# MPC23017.net
KiCad netlist of a schematic drawn in Altium Designer
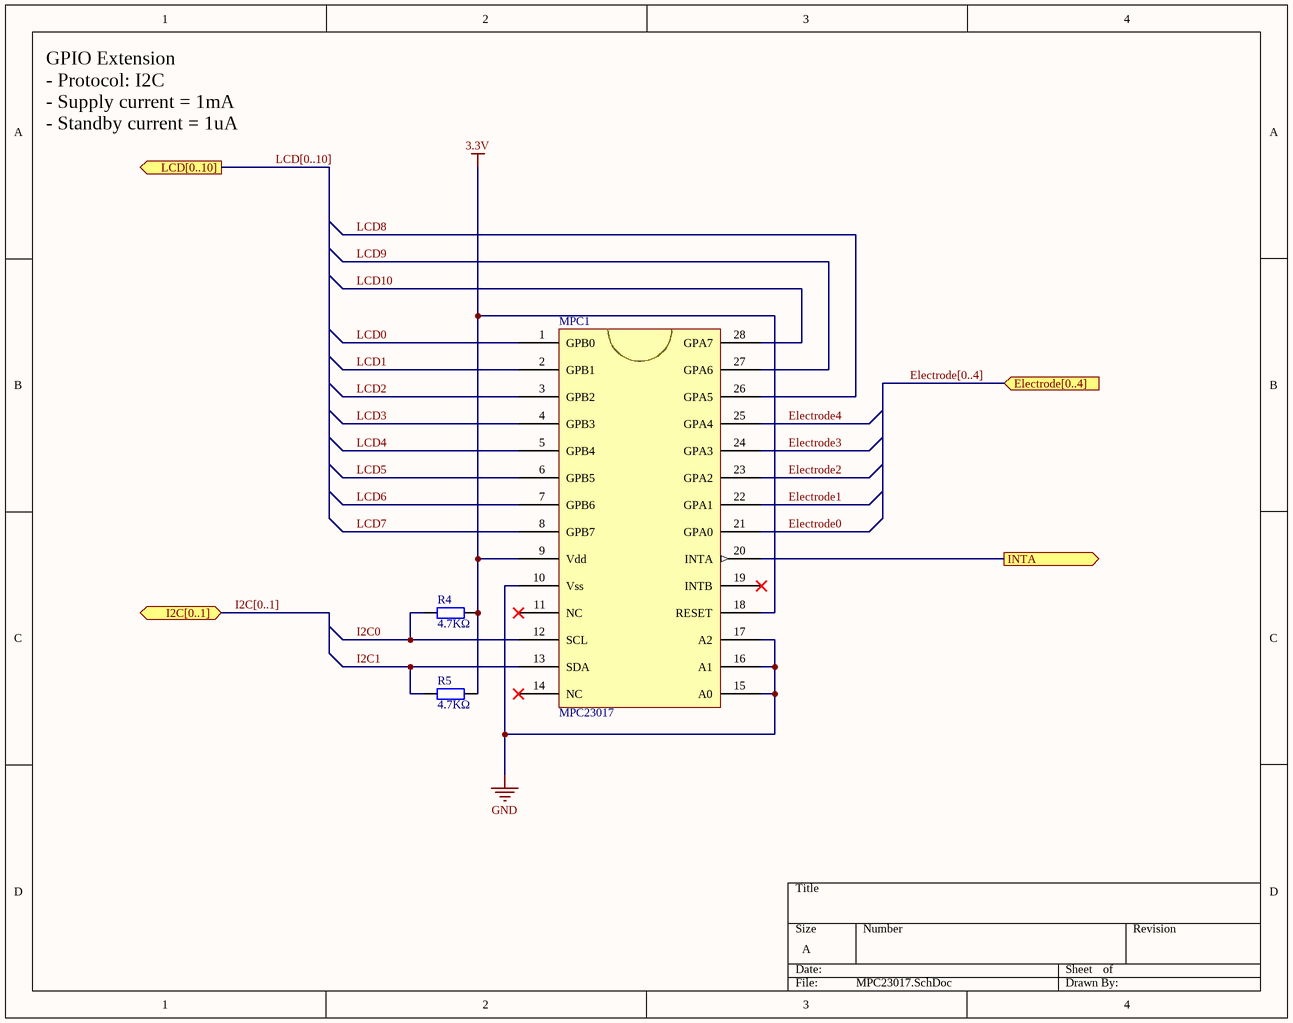
[diagram p0: MPC23017.SchDoc]

(export (version "E")
  (design (tool "Eeschema 10.0.6"))
  (components
    (comp (ref "MPC1") (value "MPC23017") (libsource (lib "MPC23017") (part "Component_1")))
    (comp (ref "R4")
      (value "4.7KΩ")
      (footprint "AXIAL-0.4")
      (description "Resistor")
      (fields (field (name "PUBLISHER") "Altium Limited"))
      (libsource (lib "Miscellaneous Devices") (part "Res2"))
    )
    (comp (ref "R5")
      (value "4.7KΩ")
      (footprint "AXIAL-0.4")
      (description "Resistor")
      (fields (field (name "PUBLISHER") "Altium Limited"))
      (libsource (lib "Miscellaneous Devices") (part "Res2"))
    )
  )
  (nets
    (net (code "1") (name "/Electrode0") (class "Default")
      (node (ref "MPC1") (pin "21") (pinfunction "GPA0_21") (pintype "passive"))
    )
    (net (code "2") (name "/Electrode1") (class "Default")
      (node (ref "MPC1") (pin "22") (pinfunction "GPA1_22") (pintype "passive"))
    )
    (net (code "3") (name "/Electrode2") (class "Default")
      (node (ref "MPC1") (pin "23") (pinfunction "GPA2_23") (pintype "passive"))
    )
    (net (code "4") (name "/Electrode3") (class "Default")
      (node (ref "MPC1") (pin "24") (pinfunction "GPA3_24") (pintype "passive"))
    )
    (net (code "5") (name "/Electrode4") (class "Default")
      (node (ref "MPC1") (pin "25") (pinfunction "GPA4_25") (pintype "passive"))
    )
    (net (code "7") (name "/I2C0") (class "Default")
      (node (ref "MPC1") (pin "12") (pinfunction "SCL_12") (pintype "passive"))
      (node (ref "R4") (pin "2") (pinfunction "2_2") (pintype "passive"))
    )
    (net (code "8") (name "/I2C1") (class "Default")
      (node (ref "MPC1") (pin "13") (pinfunction "SDA_13") (pintype "passive"))
      (node (ref "R5") (pin "2") (pinfunction "2_2") (pintype "passive"))
    )
    (net (code "10") (name "/INTA") (class "Default")
      (node (ref "MPC1") (pin "20") (pinfunction "INTA_20") (pintype "output"))
    )
    (net (code "11") (name "/LCD0") (class "Default")
      (node (ref "MPC1") (pin "1") (pinfunction "GPB0_1") (pintype "passive"))
    )
    (net (code "12") (name "/LCD1") (class "Default")
      (node (ref "MPC1") (pin "2") (pinfunction "GPB1_2") (pintype "passive"))
    )
    (net (code "13") (name "/LCD2") (class "Default")
      (node (ref "MPC1") (pin "3") (pinfunction "GPB2_3") (pintype "passive"))
    )
    (net (code "14") (name "/LCD3") (class "Default")
      (node (ref "MPC1") (pin "4") (pinfunction "GPB3_4") (pintype "passive"))
    )
    (net (code "15") (name "/LCD4") (class "Default")
      (node (ref "MPC1") (pin "5") (pinfunction "GPB4_5") (pintype "passive"))
    )
    (net (code "16") (name "/LCD5") (class "Default")
      (node (ref "MPC1") (pin "6") (pinfunction "GPB5_6") (pintype "passive"))
    )
    (net (code "17") (name "/LCD6") (class "Default")
      (node (ref "MPC1") (pin "7") (pinfunction "GPB6_7") (pintype "passive"))
    )
    (net (code "18") (name "/LCD7") (class "Default")
      (node (ref "MPC1") (pin "8") (pinfunction "GPB7_8") (pintype "passive"))
    )
    (net (code "19") (name "/LCD8") (class "Default")
      (node (ref "MPC1") (pin "26") (pinfunction "GPA5_26") (pintype "passive"))
    )
    (net (code "20") (name "/LCD9") (class "Default")
      (node (ref "MPC1") (pin "27") (pinfunction "GPA6_27") (pintype "passive"))
    )
    (net (code "21") (name "/LCD10") (class "Default")
      (node (ref "MPC1") (pin "28") (pinfunction "GPA7_28") (pintype "passive"))
    )
    (net (code "23") (name "3.3V") (class "Default")
      (node (ref "MPC1") (pin "18") (pinfunction "RESET_18") (pintype "passive"))
      (node (ref "MPC1") (pin "9") (pinfunction "Vdd_9") (pintype "passive"))
      (node (ref "R4") (pin "1") (pinfunction "1_1") (pintype "passive"))
      (node (ref "R5") (pin "1") (pinfunction "1_1") (pintype "passive"))
    )
    (net (code "24") (name "GND") (class "Default")
      (node (ref "MPC1") (pin "10") (pinfunction "Vss_10") (pintype "passive"))
      (node (ref "MPC1") (pin "15") (pinfunction "A0_15") (pintype "passive"))
      (node (ref "MPC1") (pin "16") (pinfunction "A1_16") (pintype "passive"))
      (node (ref "MPC1") (pin "17") (pinfunction "A2_17") (pintype "passive"))
    )
    (net (code "25") (name "unconnected-(MPC1-INTB-Pad19)") (class "Default")
      (node (ref "MPC1") (pin "19") (pinfunction "INTB_19") (pintype "passive+no_connect"))
    )
    (net (code "26") (name "unconnected-(MPC1-NC-Pad11)") (class "Default")
      (node (ref "MPC1") (pin "11") (pinfunction "NC_11") (pintype "passive+no_connect"))
    )
    (net (code "27") (name "unconnected-(MPC1-NC-Pad14)") (class "Default")
      (node (ref "MPC1") (pin "14") (pinfunction "NC_14") (pintype "passive+no_connect"))
    )
  )
)
